# bottom_PCB_mini.net
KiCad netlist of a schematic drawn in EAGLE
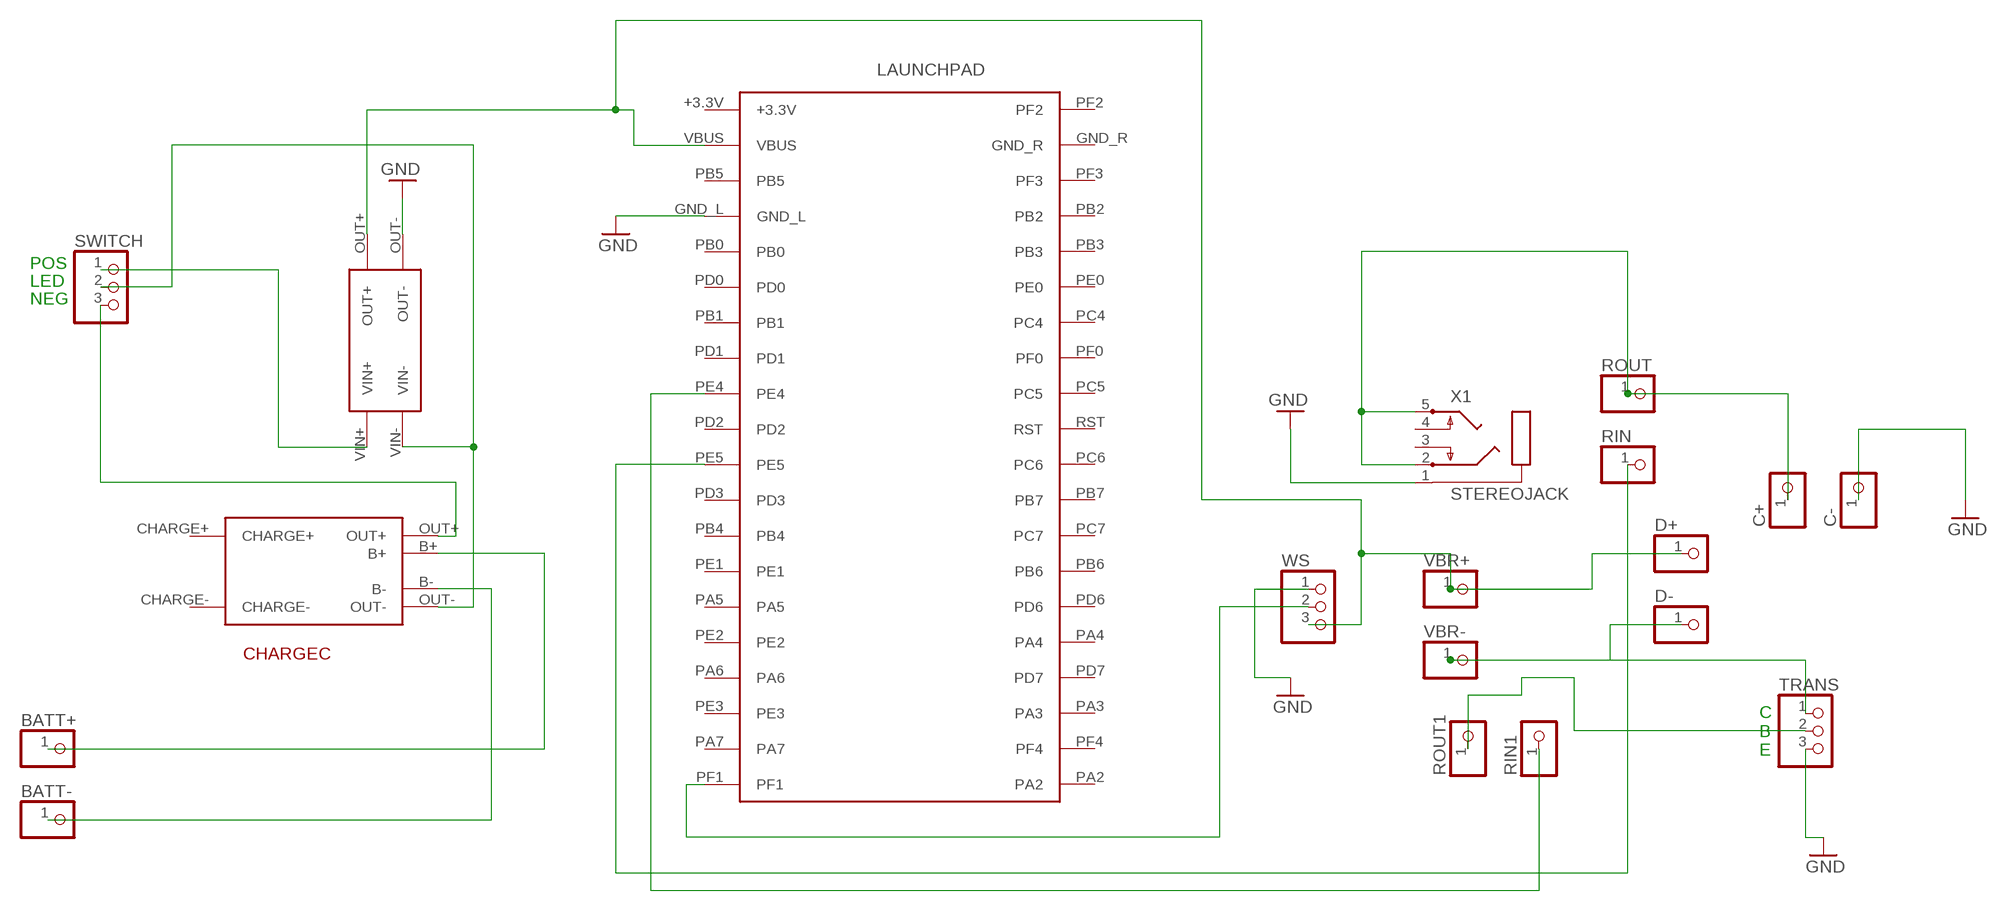
[diagram p0: schematic, sheet 1]

(export (version "E")
  (design (tool "Eeschema 10.0.6"))
  (components
    (comp (ref "BATT+")
      (value "PINHD-1X1CB")
      (footprint "eagle-import:1X01-CLEANBIG")
      (libsource (lib "eagle-import") (part "PINHD-1X1CB"))
    )
    (comp (ref "BATT-")
      (value "PINHD-1X1CB")
      (footprint "eagle-import:1X01-CLEANBIG")
      (libsource (lib "eagle-import") (part "PINHD-1X1CB"))
    )
    (comp (ref "C+")
      (value "PINHD-1X1CB")
      (footprint "eagle-import:1X01-CLEANBIG")
      (libsource (lib "eagle-import") (part "PINHD-1X1CB"))
    )
    (comp (ref "C-")
      (value "PINHD-1X1CB")
      (footprint "eagle-import:1X01-CLEANBIG")
      (libsource (lib "eagle-import") (part "PINHD-1X1CB"))
    )
    (comp (ref "CHARGEC")
      (value "18650CCEBAY")
      (footprint "eagle-import:18650CCEBAY")
      (libsource (lib "eagle-import") (part "18650CCEBAY"))
    )
    (comp (ref "D+")
      (value "PINHD-1X1CB")
      (footprint "eagle-import:1X01-CLEANBIG")
      (libsource (lib "eagle-import") (part "PINHD-1X1CB"))
    )
    (comp (ref "D-")
      (value "PINHD-1X1CB")
      (footprint "eagle-import:1X01-CLEANBIG")
      (libsource (lib "eagle-import") (part "PINHD-1X1CB"))
    )
    (comp (ref "LAUNCHPAD")
      (value "TM4CTM4C")
      (footprint "eagle-import:1_05X2MM")
      (libsource (lib "eagle-import") (part "TM4CTM4C"))
    )
    (comp (ref "RIN")
      (value "PINHD-1X1CB")
      (footprint "eagle-import:1X01-CLEANBIG")
      (libsource (lib "eagle-import") (part "PINHD-1X1CB"))
    )
    (comp (ref "RIN1")
      (value "PINHD-1X1CB")
      (footprint "eagle-import:1X01-CLEANBIG")
      (libsource (lib "eagle-import") (part "PINHD-1X1CB"))
    )
    (comp (ref "ROUT")
      (value "PINHD-1X1CB")
      (footprint "eagle-import:1X01-CLEANBIG")
      (libsource (lib "eagle-import") (part "PINHD-1X1CB"))
    )
    (comp (ref "ROUT1")
      (value "PINHD-1X1CB")
      (footprint "eagle-import:1X01-CLEANBIG")
      (libsource (lib "eagle-import") (part "PINHD-1X1CB"))
    )
    (comp (ref "SWITCH")
      (value "PINHD-1X3CB")
      (footprint "eagle-import:1X03-CLEANBIG")
      (libsource (lib "eagle-import") (part "PINHD-1X3CB"))
    )
    (comp (ref "TRANS")
      (value "PINHD-1X3CB")
      (footprint "eagle-import:1X03-CLEANBIG")
      (libsource (lib "eagle-import") (part "PINHD-1X3CB"))
    )
    (comp (ref "VBR+")
      (value "PINHD-1X1CB")
      (footprint "eagle-import:1X01-CLEANBIG")
      (libsource (lib "eagle-import") (part "PINHD-1X1CB"))
    )
    (comp (ref "VBR-")
      (value "PINHD-1X1CB")
      (footprint "eagle-import:1X01-CLEANBIG")
      (libsource (lib "eagle-import") (part "PINHD-1X1CB"))
    )
    (comp (ref "VREG")
      (value "MT3608_EBAY")
      (footprint "eagle-import:MT3608_EBAY")
      (libsource (lib "eagle-import") (part "MT3608_EBAY"))
    )
    (comp (ref "WS")
      (value "PINHD-1X3CB")
      (footprint "eagle-import:1X03-CLEANBIG")
      (libsource (lib "eagle-import") (part "PINHD-1X3CB"))
    )
    (comp (ref "X1")
      (value "STEREOJACK")
      (footprint "eagle-import:STX3100")
      (libsource (lib "eagle-import") (part "STEREOJACK"))
    )
  )
  (nets
    (net (code "1") (name "/+3.3V") (class "Default")
      (node (ref "LAUNCHPAD") (pin "+3.3V") (pinfunction "+3.3V_+3.3V") (pintype "power_in"))
    )
    (net (code "2") (name "/GND_R") (class "Default")
      (node (ref "LAUNCHPAD") (pin "GND_R") (pinfunction "GND_R_GND_R") (pintype "power_in"))
    )
    (net (code "3") (name "GND") (class "Default")
      (node (ref "C-") (pin "1") (pinfunction "1_1") (pintype "passive"))
      (node (ref "LAUNCHPAD") (pin "GND_L") (pinfunction "GND_L_GND_L") (pintype "power_in"))
      (node (ref "TRANS") (pin "3") (pinfunction "3_3") (pintype "passive"))
      (node (ref "VREG") (pin "OUT-") (pinfunction "OUT-_OUT-") (pintype "bidirectional"))
      (node (ref "WS") (pin "1") (pinfunction "1_1") (pintype "passive"))
      (node (ref "X1") (pin "1") (pinfunction "1_1") (pintype "passive"))
    )
    (net (code "4") (name "Net-(BATT+-Pad1)") (class "Default")
      (node (ref "BATT+") (pin "1") (pinfunction "1_1") (pintype "passive"))
      (node (ref "CHARGEC") (pin "B+") (pinfunction "B+_B+") (pintype "bidirectional"))
    )
    (net (code "5") (name "Net-(BATT--Pad1)") (class "Default")
      (node (ref "BATT-") (pin "1") (pinfunction "1_1") (pintype "passive"))
      (node (ref "CHARGEC") (pin "B-") (pinfunction "B-_B-") (pintype "bidirectional"))
    )
    (net (code "6") (name "Net-(C+-Pad1)") (class "Default")
      (node (ref "C+") (pin "1") (pinfunction "1_1") (pintype "passive"))
      (node (ref "ROUT") (pin "1") (pinfunction "1_1") (pintype "passive"))
      (node (ref "X1") (pin "2") (pinfunction "2_2") (pintype "passive"))
      (node (ref "X1") (pin "5") (pinfunction "5_5") (pintype "passive"))
    )
    (net (code "7") (name "Net-(CHARGEC-PadOUT+)") (class "Default")
      (node (ref "CHARGEC") (pin "OUT+") (pinfunction "OUT+_OUT+") (pintype "bidirectional"))
      (node (ref "SWITCH") (pin "3") (pinfunction "3_3") (pintype "passive"))
    )
    (net (code "8") (name "Net-(CHARGEC-PadOUT-)") (class "Default")
      (node (ref "CHARGEC") (pin "OUT-") (pinfunction "OUT-_OUT-") (pintype "bidirectional"))
      (node (ref "SWITCH") (pin "2") (pinfunction "2_2") (pintype "passive"))
      (node (ref "VREG") (pin "VIN-") (pinfunction "VIN-_VIN-") (pintype "bidirectional"))
    )
    (net (code "9") (name "Net-(D+-Pad1)") (class "Default")
      (node (ref "D+") (pin "1") (pinfunction "1_1") (pintype "passive"))
      (node (ref "LAUNCHPAD") (pin "VBUS") (pinfunction "VBUS_VBUS") (pintype "power_in"))
      (node (ref "VBR+") (pin "1") (pinfunction "1_1") (pintype "passive"))
      (node (ref "VREG") (pin "OUT+") (pinfunction "OUT+_OUT+") (pintype "bidirectional"))
      (node (ref "WS") (pin "3") (pinfunction "3_3") (pintype "passive"))
    )
    (net (code "10") (name "Net-(D--Pad1)") (class "Default")
      (node (ref "D-") (pin "1") (pinfunction "1_1") (pintype "passive"))
      (node (ref "TRANS") (pin "1") (pinfunction "1_1") (pintype "passive"))
      (node (ref "VBR-") (pin "1") (pinfunction "1_1") (pintype "passive"))
    )
    (net (code "11") (name "Net-(LAUNCHPAD-PadPE4)") (class "Default")
      (node (ref "LAUNCHPAD") (pin "PE4") (pinfunction "PE4_PE4") (pintype "bidirectional"))
      (node (ref "RIN1") (pin "1") (pinfunction "1_1") (pintype "passive"))
    )
    (net (code "12") (name "Net-(LAUNCHPAD-PadPE5)") (class "Default")
      (node (ref "LAUNCHPAD") (pin "PE5") (pinfunction "PE5_PE5") (pintype "bidirectional"))
      (node (ref "RIN") (pin "1") (pinfunction "1_1") (pintype "passive"))
    )
    (net (code "13") (name "Net-(LAUNCHPAD-PadPF1)") (class "Default")
      (node (ref "LAUNCHPAD") (pin "PF1") (pinfunction "PF1_PF1") (pintype "bidirectional"))
      (node (ref "WS") (pin "2") (pinfunction "2_2") (pintype "passive"))
    )
    (net (code "14") (name "Net-(ROUT1-Pad1)") (class "Default")
      (node (ref "ROUT1") (pin "1") (pinfunction "1_1") (pintype "passive"))
      (node (ref "TRANS") (pin "2") (pinfunction "2_2") (pintype "passive"))
    )
    (net (code "15") (name "Net-(SWITCH-Pad1)") (class "Default")
      (node (ref "SWITCH") (pin "1") (pinfunction "1_1") (pintype "passive"))
      (node (ref "VREG") (pin "VIN+") (pinfunction "VIN+_VIN+") (pintype "bidirectional"))
    )
    (net (code "16") (name "unconnected-(CHARGEC-PadCHARGE+)") (class "Default")
      (node (ref "CHARGEC") (pin "CHARGE+") (pinfunction "CHARGE+_CHARGE+") (pintype "bidirectional"))
    )
    (net (code "17") (name "unconnected-(CHARGEC-PadCHARGE-)") (class "Default")
      (node (ref "CHARGEC") (pin "CHARGE-") (pinfunction "CHARGE-_CHARGE-") (pintype "bidirectional"))
    )
    (net (code "18") (name "unconnected-(LAUNCHPAD-PadPA2)") (class "Default")
      (node (ref "LAUNCHPAD") (pin "PA2") (pinfunction "PA2_PA2") (pintype "bidirectional"))
    )
    (net (code "19") (name "unconnected-(LAUNCHPAD-PadPA3)") (class "Default")
      (node (ref "LAUNCHPAD") (pin "PA3") (pinfunction "PA3_PA3") (pintype "bidirectional"))
    )
    (net (code "20") (name "unconnected-(LAUNCHPAD-PadPA4)") (class "Default")
      (node (ref "LAUNCHPAD") (pin "PA4") (pinfunction "PA4_PA4") (pintype "bidirectional"))
    )
    (net (code "21") (name "unconnected-(LAUNCHPAD-PadPA5)") (class "Default")
      (node (ref "LAUNCHPAD") (pin "PA5") (pinfunction "PA5_PA5") (pintype "bidirectional"))
    )
    (net (code "22") (name "unconnected-(LAUNCHPAD-PadPA6)") (class "Default")
      (node (ref "LAUNCHPAD") (pin "PA6") (pinfunction "PA6_PA6") (pintype "bidirectional"))
    )
    (net (code "23") (name "unconnected-(LAUNCHPAD-PadPA7)") (class "Default")
      (node (ref "LAUNCHPAD") (pin "PA7") (pinfunction "PA7_PA7") (pintype "bidirectional"))
    )
    (net (code "24") (name "unconnected-(LAUNCHPAD-PadPB0)") (class "Default")
      (node (ref "LAUNCHPAD") (pin "PB0") (pinfunction "PB0_PB0") (pintype "bidirectional"))
    )
    (net (code "25") (name "unconnected-(LAUNCHPAD-PadPB1)") (class "Default")
      (node (ref "LAUNCHPAD") (pin "PB1") (pinfunction "PB1_PB1") (pintype "bidirectional"))
    )
    (net (code "26") (name "unconnected-(LAUNCHPAD-PadPB2)") (class "Default")
      (node (ref "LAUNCHPAD") (pin "PB2") (pinfunction "PB2_PB2") (pintype "bidirectional"))
    )
    (net (code "27") (name "unconnected-(LAUNCHPAD-PadPB3)") (class "Default")
      (node (ref "LAUNCHPAD") (pin "PB3") (pinfunction "PB3_PB3") (pintype "bidirectional"))
    )
    (net (code "28") (name "unconnected-(LAUNCHPAD-PadPB4)") (class "Default")
      (node (ref "LAUNCHPAD") (pin "PB4") (pinfunction "PB4_PB4") (pintype "bidirectional"))
    )
    (net (code "29") (name "unconnected-(LAUNCHPAD-PadPB5)") (class "Default")
      (node (ref "LAUNCHPAD") (pin "PB5") (pinfunction "PB5_PB5") (pintype "bidirectional"))
    )
    (net (code "30") (name "unconnected-(LAUNCHPAD-PadPB6)") (class "Default")
      (node (ref "LAUNCHPAD") (pin "PB6") (pinfunction "PB6_PB6") (pintype "bidirectional"))
    )
    (net (code "31") (name "unconnected-(LAUNCHPAD-PadPB7)") (class "Default")
      (node (ref "LAUNCHPAD") (pin "PB7") (pinfunction "PB7_PB7") (pintype "bidirectional"))
    )
    (net (code "32") (name "unconnected-(LAUNCHPAD-PadPC4)") (class "Default")
      (node (ref "LAUNCHPAD") (pin "PC4") (pinfunction "PC4_PC4") (pintype "bidirectional"))
    )
    (net (code "33") (name "unconnected-(LAUNCHPAD-PadPC5)") (class "Default")
      (node (ref "LAUNCHPAD") (pin "PC5") (pinfunction "PC5_PC5") (pintype "bidirectional"))
    )
    (net (code "34") (name "unconnected-(LAUNCHPAD-PadPC6)") (class "Default")
      (node (ref "LAUNCHPAD") (pin "PC6") (pinfunction "PC6_PC6") (pintype "bidirectional"))
    )
    (net (code "35") (name "unconnected-(LAUNCHPAD-PadPC7)") (class "Default")
      (node (ref "LAUNCHPAD") (pin "PC7") (pinfunction "PC7_PC7") (pintype "bidirectional"))
    )
    (net (code "36") (name "unconnected-(LAUNCHPAD-PadPD0)") (class "Default")
      (node (ref "LAUNCHPAD") (pin "PD0") (pinfunction "PD0_PD0") (pintype "bidirectional"))
    )
    (net (code "37") (name "unconnected-(LAUNCHPAD-PadPD1)") (class "Default")
      (node (ref "LAUNCHPAD") (pin "PD1") (pinfunction "PD1_PD1") (pintype "bidirectional"))
    )
    (net (code "38") (name "unconnected-(LAUNCHPAD-PadPD2)") (class "Default")
      (node (ref "LAUNCHPAD") (pin "PD2") (pinfunction "PD2_PD2") (pintype "bidirectional"))
    )
    (net (code "39") (name "unconnected-(LAUNCHPAD-PadPD3)") (class "Default")
      (node (ref "LAUNCHPAD") (pin "PD3") (pinfunction "PD3_PD3") (pintype "bidirectional"))
    )
    (net (code "40") (name "unconnected-(LAUNCHPAD-PadPD6)") (class "Default")
      (node (ref "LAUNCHPAD") (pin "PD6") (pinfunction "PD6_PD6") (pintype "bidirectional"))
    )
    (net (code "41") (name "unconnected-(LAUNCHPAD-PadPD7)") (class "Default")
      (node (ref "LAUNCHPAD") (pin "PD7") (pinfunction "PD7_PD7") (pintype "bidirectional"))
    )
    (net (code "42") (name "unconnected-(LAUNCHPAD-PadPE0)") (class "Default")
      (node (ref "LAUNCHPAD") (pin "PE0") (pinfunction "PE0_PE0") (pintype "bidirectional"))
    )
    (net (code "43") (name "unconnected-(LAUNCHPAD-PadPE1)") (class "Default")
      (node (ref "LAUNCHPAD") (pin "PE1") (pinfunction "PE1_PE1") (pintype "bidirectional"))
    )
    (net (code "44") (name "unconnected-(LAUNCHPAD-PadPE2)") (class "Default")
      (node (ref "LAUNCHPAD") (pin "PE2") (pinfunction "PE2_PE2") (pintype "bidirectional"))
    )
    (net (code "45") (name "unconnected-(LAUNCHPAD-PadPE3)") (class "Default")
      (node (ref "LAUNCHPAD") (pin "PE3") (pinfunction "PE3_PE3") (pintype "bidirectional"))
    )
    (net (code "46") (name "unconnected-(LAUNCHPAD-PadPF0)") (class "Default")
      (node (ref "LAUNCHPAD") (pin "PF0") (pinfunction "PF0_PF0") (pintype "bidirectional"))
    )
    (net (code "47") (name "unconnected-(LAUNCHPAD-PadPF2)") (class "Default")
      (node (ref "LAUNCHPAD") (pin "PF2") (pinfunction "PF2_PF2") (pintype "bidirectional"))
    )
    (net (code "48") (name "unconnected-(LAUNCHPAD-PadPF3)") (class "Default")
      (node (ref "LAUNCHPAD") (pin "PF3") (pinfunction "PF3_PF3") (pintype "bidirectional"))
    )
    (net (code "49") (name "unconnected-(LAUNCHPAD-PadPF4)") (class "Default")
      (node (ref "LAUNCHPAD") (pin "PF4") (pinfunction "PF4_PF4") (pintype "bidirectional"))
    )
    (net (code "50") (name "unconnected-(LAUNCHPAD-PadRST)") (class "Default")
      (node (ref "LAUNCHPAD") (pin "RST") (pinfunction "RST_RST") (pintype "bidirectional"))
    )
    (net (code "51") (name "unconnected-(X1-Pad3)") (class "Default")
      (node (ref "X1") (pin "3") (pinfunction "3_3") (pintype "passive"))
    )
    (net (code "52") (name "unconnected-(X1-Pad4)") (class "Default")
      (node (ref "X1") (pin "4") (pinfunction "4_4") (pintype "passive"))
    )
  )
)
